# aa8028.net
KiCad netlist of a schematic drawn in Altium Designer
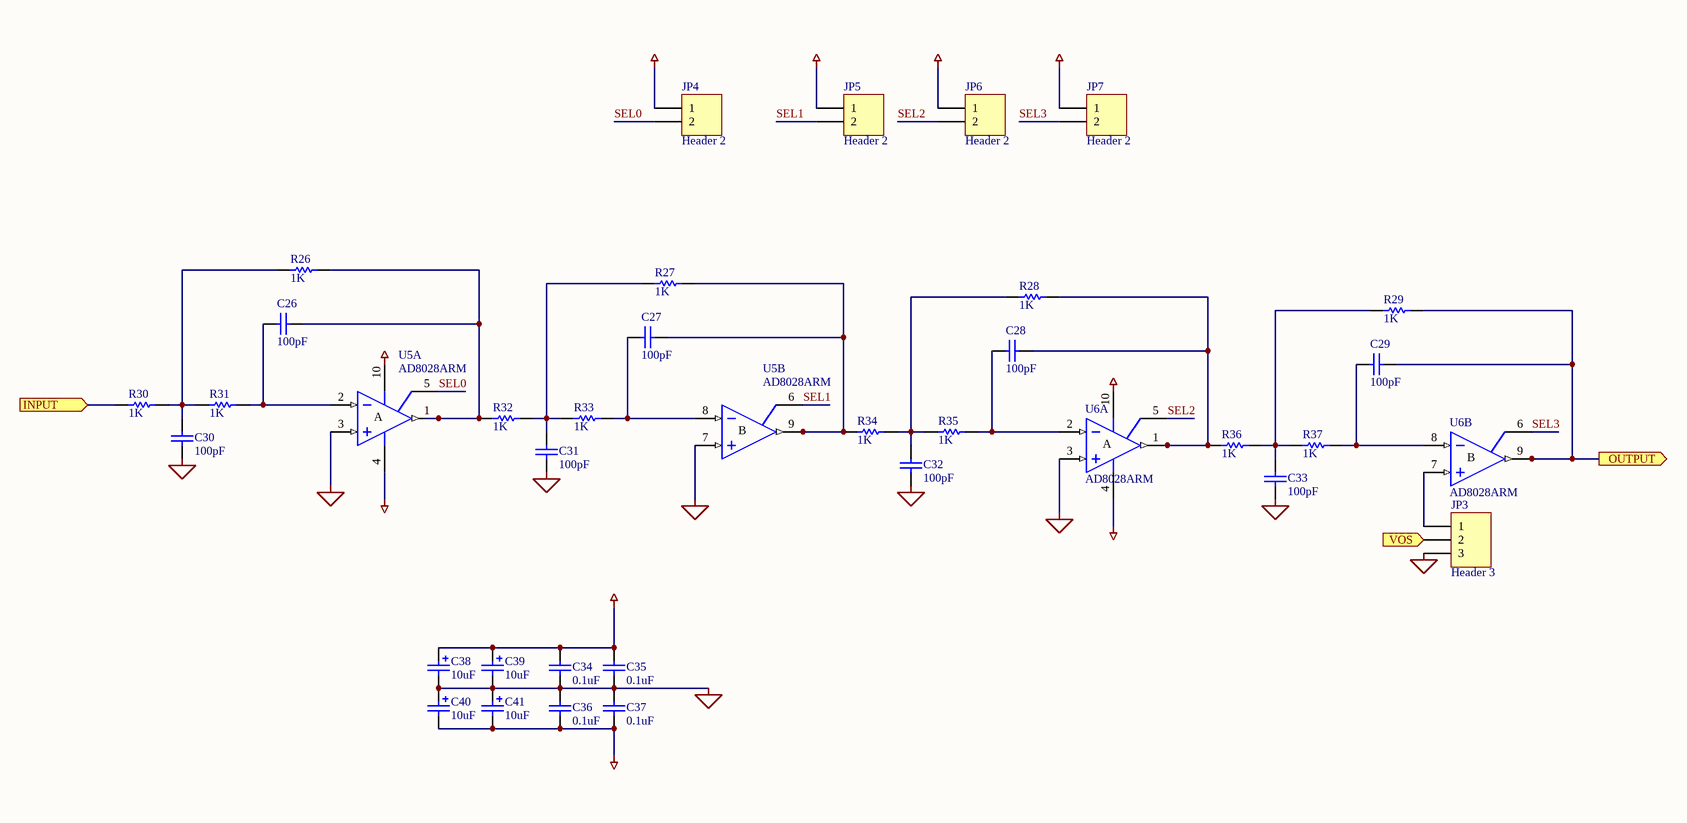
[diagram p0: aa8028.SCHDOC]

(export (version "E")
  (design (tool "Eeschema 10.0.6"))
  (components
    (comp (ref "C26")
      (value "Cap")
      (footprint "CC3216-1206")
      (description "Capacitor")
      (fields
        (field (name "MANUFACTURER") "Generic Components")
        (field (name "ALTIUM_VALUE") "100pF")
        (field (name "PUBLISHER") "Altium Limited")
      )
      (libsource (lib "Miscellaneous Devices") (part "Cap"))
    )
    (comp (ref "C27")
      (value "Cap")
      (footprint "CC3216-1206")
      (description "Capacitor")
      (fields
        (field (name "MANUFACTURER") "Generic Components")
        (field (name "ALTIUM_VALUE") "100pF")
        (field (name "PUBLISHER") "Altium Limited")
      )
      (libsource (lib "Miscellaneous Devices") (part "Cap"))
    )
    (comp (ref "C28")
      (value "Cap")
      (footprint "CC3216-1206")
      (description "Capacitor")
      (fields
        (field (name "MANUFACTURER") "Generic Components")
        (field (name "ALTIUM_VALUE") "100pF")
        (field (name "PUBLISHER") "Altium Limited")
      )
      (libsource (lib "Miscellaneous Devices") (part "Cap"))
    )
    (comp (ref "C29")
      (value "Cap")
      (footprint "CC3216-1206")
      (description "Capacitor")
      (fields
        (field (name "MANUFACTURER") "Generic Components")
        (field (name "ALTIUM_VALUE") "100pF")
        (field (name "PUBLISHER") "Altium Limited")
      )
      (libsource (lib "Miscellaneous Devices") (part "Cap"))
    )
    (comp (ref "C30")
      (value "Cap")
      (footprint "CC3216-1206")
      (description "Capacitor")
      (fields
        (field (name "MANUFACTURER") "Generic Components")
        (field (name "ALTIUM_VALUE") "100pF")
        (field (name "PUBLISHER") "Altium Limited")
      )
      (libsource (lib "Miscellaneous Devices") (part "Cap"))
    )
    (comp (ref "C31")
      (value "Cap")
      (footprint "CC3216-1206")
      (description "Capacitor")
      (fields
        (field (name "MANUFACTURER") "Generic Components")
        (field (name "ALTIUM_VALUE") "100pF")
        (field (name "PUBLISHER") "Altium Limited")
      )
      (libsource (lib "Miscellaneous Devices") (part "Cap"))
    )
    (comp (ref "C32")
      (value "Cap")
      (footprint "CC3216-1206")
      (description "Capacitor")
      (fields
        (field (name "MANUFACTURER") "Generic Components")
        (field (name "ALTIUM_VALUE") "100pF")
        (field (name "PUBLISHER") "Altium Limited")
      )
      (libsource (lib "Miscellaneous Devices") (part "Cap"))
    )
    (comp (ref "C33")
      (value "Cap")
      (footprint "CC3216-1206")
      (description "Capacitor")
      (fields
        (field (name "MANUFACTURER") "Generic Components")
        (field (name "ALTIUM_VALUE") "100pF")
        (field (name "PUBLISHER") "Altium Limited")
      )
      (libsource (lib "Miscellaneous Devices") (part "Cap"))
    )
    (comp (ref "C34")
      (value "Cap")
      (footprint "CC1608-0603")
      (description "Capacitor")
      (fields
        (field (name "MANUFACTURER") "Generic Components")
        (field (name "ALTIUM_VALUE") "0.1uF")
        (field (name "PUBLISHER") "Altium Limited")
      )
      (libsource (lib "Miscellaneous Devices") (part "Cap"))
    )
    (comp (ref "C35")
      (value "Cap")
      (footprint "CC1608-0603")
      (description "Capacitor")
      (fields
        (field (name "MANUFACTURER") "Generic Components")
        (field (name "ALTIUM_VALUE") "0.1uF")
        (field (name "PUBLISHER") "Altium Limited")
      )
      (libsource (lib "Miscellaneous Devices") (part "Cap"))
    )
    (comp (ref "C36")
      (value "Cap")
      (footprint "CC1608-0603")
      (description "Capacitor")
      (fields
        (field (name "MANUFACTURER") "Generic Components")
        (field (name "ALTIUM_VALUE") "0.1uF")
        (field (name "PUBLISHER") "Altium Limited")
      )
      (libsource (lib "Miscellaneous Devices") (part "Cap"))
    )
    (comp (ref "C37")
      (value "Cap")
      (footprint "CC1608-0603")
      (description "Capacitor")
      (fields
        (field (name "MANUFACTURER") "Generic Components")
        (field (name "ALTIUM_VALUE") "0.1uF")
        (field (name "PUBLISHER") "Altium Limited")
      )
      (libsource (lib "Miscellaneous Devices") (part "Cap"))
    )
    (comp (ref "C38")
      (value "Cap Pol1")
      (footprint "TC7360-2924")
      (description "Polarized Capacitor (Radial)")
      (fields
        (field (name "MANUFACTURER") "Generic Components")
        (field (name "ALTIUM_VALUE") "10uF")
        (field (name "PUBLISHER") "Altium Limited")
      )
      (libsource (lib "Miscellaneous Devices") (part "Cap Pol1"))
    )
    (comp (ref "C39")
      (value "Cap Pol1")
      (footprint "TC7360-2924")
      (description "Polarized Capacitor (Radial)")
      (fields
        (field (name "MANUFACTURER") "Generic Components")
        (field (name "ALTIUM_VALUE") "10uF")
        (field (name "PUBLISHER") "Altium Limited")
      )
      (libsource (lib "Miscellaneous Devices") (part "Cap Pol1"))
    )
    (comp (ref "C40")
      (value "Cap Pol1")
      (footprint "TC7360-2924")
      (description "Polarized Capacitor (Radial)")
      (fields
        (field (name "MANUFACTURER") "Generic Components")
        (field (name "ALTIUM_VALUE") "10uF")
        (field (name "PUBLISHER") "Altium Limited")
      )
      (libsource (lib "Miscellaneous Devices") (part "Cap Pol1"))
    )
    (comp (ref "C41")
      (value "Cap Pol1")
      (footprint "TC7360-2924")
      (description "Polarized Capacitor (Radial)")
      (fields
        (field (name "MANUFACTURER") "Generic Components")
        (field (name "ALTIUM_VALUE") "10uF")
        (field (name "PUBLISHER") "Altium Limited")
      )
      (libsource (lib "Miscellaneous Devices") (part "Cap Pol1"))
    )
    (comp (ref "JP3")
      (value "Header 3")
      (footprint "HDR1X3")
      (description "Header, 3-Pin")
      (fields (field (name "MANUFACTURER") "Generic Components") (field (name "PUBLISHER") "Altium Limited"))
      (libsource (lib "Miscellaneous Connectors") (part "Header 3"))
    )
    (comp (ref "JP4")
      (value "Header 2")
      (footprint "HDR1X2")
      (description "Header, 2-Pin")
      (fields (field (name "MANUFACTURER") "Generic Components") (field (name "PUBLISHER") "Altium Limited"))
      (libsource (lib "Miscellaneous Connectors") (part "Header 2"))
    )
    (comp (ref "JP5")
      (value "Header 2")
      (footprint "HDR1X2")
      (description "Header, 2-Pin")
      (fields (field (name "MANUFACTURER") "Generic Components") (field (name "PUBLISHER") "Altium Limited"))
      (libsource (lib "Miscellaneous Connectors") (part "Header 2"))
    )
    (comp (ref "JP6")
      (value "Header 2")
      (footprint "HDR1X2")
      (description "Header, 2-Pin")
      (fields (field (name "MANUFACTURER") "Generic Components") (field (name "PUBLISHER") "Altium Limited"))
      (libsource (lib "Miscellaneous Connectors") (part "Header 2"))
    )
    (comp (ref "JP7")
      (value "Header 2")
      (footprint "HDR1X2")
      (description "Header, 2-Pin")
      (fields (field (name "MANUFACTURER") "Generic Components") (field (name "PUBLISHER") "Altium Limited"))
      (libsource (lib "Miscellaneous Connectors") (part "Header 2"))
    )
    (comp (ref "R26")
      (value "Res1")
      (footprint "CC2012-0805")
      (description "Resistor")
      (fields
        (field (name "MANUFACTURER") "Generic Components")
        (field (name "ALTIUM_VALUE") "1K")
        (field (name "PUBLISHER") "Altium Limited")
      )
      (libsource (lib "Miscellaneous Devices") (part "Res1"))
    )
    (comp (ref "R27")
      (value "Res1")
      (footprint "CC2012-0805")
      (description "Resistor")
      (fields
        (field (name "MANUFACTURER") "Generic Components")
        (field (name "ALTIUM_VALUE") "1K")
        (field (name "PUBLISHER") "Altium Limited")
      )
      (libsource (lib "Miscellaneous Devices") (part "Res1"))
    )
    (comp (ref "R28")
      (value "Res1")
      (footprint "CC2012-0805")
      (description "Resistor")
      (fields
        (field (name "MANUFACTURER") "Generic Components")
        (field (name "ALTIUM_VALUE") "1K")
        (field (name "PUBLISHER") "Altium Limited")
      )
      (libsource (lib "Miscellaneous Devices") (part "Res1"))
    )
    (comp (ref "R29")
      (value "Res1")
      (footprint "CC2012-0805")
      (description "Resistor")
      (fields
        (field (name "MANUFACTURER") "Generic Components")
        (field (name "ALTIUM_VALUE") "1K")
        (field (name "PUBLISHER") "Altium Limited")
      )
      (libsource (lib "Miscellaneous Devices") (part "Res1"))
    )
    (comp (ref "R30")
      (value "Res1")
      (footprint "CC2012-0805")
      (description "Resistor")
      (fields
        (field (name "MANUFACTURER") "Generic Components")
        (field (name "ALTIUM_VALUE") "1K")
        (field (name "PUBLISHER") "Altium Limited")
      )
      (libsource (lib "Miscellaneous Devices") (part "Res1"))
    )
    (comp (ref "R31")
      (value "Res1")
      (footprint "CC2012-0805")
      (description "Resistor")
      (fields
        (field (name "MANUFACTURER") "Generic Components")
        (field (name "ALTIUM_VALUE") "1K")
        (field (name "PUBLISHER") "Altium Limited")
      )
      (libsource (lib "Miscellaneous Devices") (part "Res1"))
    )
    (comp (ref "R32")
      (value "Res1")
      (footprint "CC2012-0805")
      (description "Resistor")
      (fields
        (field (name "MANUFACTURER") "Generic Components")
        (field (name "ALTIUM_VALUE") "1K")
        (field (name "PUBLISHER") "Altium Limited")
      )
      (libsource (lib "Miscellaneous Devices") (part "Res1"))
    )
    (comp (ref "R33")
      (value "Res1")
      (footprint "CC2012-0805")
      (description "Resistor")
      (fields
        (field (name "MANUFACTURER") "Generic Components")
        (field (name "ALTIUM_VALUE") "1K")
        (field (name "PUBLISHER") "Altium Limited")
      )
      (libsource (lib "Miscellaneous Devices") (part "Res1"))
    )
    (comp (ref "R34")
      (value "Res1")
      (footprint "CC2012-0805")
      (description "Resistor")
      (fields
        (field (name "MANUFACTURER") "Generic Components")
        (field (name "ALTIUM_VALUE") "1K")
        (field (name "PUBLISHER") "Altium Limited")
      )
      (libsource (lib "Miscellaneous Devices") (part "Res1"))
    )
    (comp (ref "R35")
      (value "Res1")
      (footprint "CC2012-0805")
      (description "Resistor")
      (fields
        (field (name "MANUFACTURER") "Generic Components")
        (field (name "ALTIUM_VALUE") "1K")
        (field (name "PUBLISHER") "Altium Limited")
      )
      (libsource (lib "Miscellaneous Devices") (part "Res1"))
    )
    (comp (ref "R36")
      (value "Res1")
      (footprint "CC2012-0805")
      (description "Resistor")
      (fields
        (field (name "MANUFACTURER") "Generic Components")
        (field (name "ALTIUM_VALUE") "1K")
        (field (name "PUBLISHER") "Altium Limited")
      )
      (libsource (lib "Miscellaneous Devices") (part "Res1"))
    )
    (comp (ref "R37")
      (value "Res1")
      (footprint "CC2012-0805")
      (description "Resistor")
      (fields
        (field (name "MANUFACTURER") "Generic Components")
        (field (name "ALTIUM_VALUE") "1K")
        (field (name "PUBLISHER") "Altium Limited")
      )
      (libsource (lib "Miscellaneous Devices") (part "Res1"))
    )
    (comp (ref "U5")
      (value "AD8028ARM")
      (footprint "TSSO3x5-G10")
      (description "Analog Devices Low Distortion, High Speed RRIO OA")
      (libsource (lib "My devices") (part "AD8028ARM"))
    )
    (comp (ref "U6")
      (value "AD8028ARM")
      (footprint "TSSO3x5-G10")
      (description "Analog Devices Low Distortion, High Speed RRIO OA")
      (libsource (lib "My devices") (part "AD8028ARM"))
    )
  )
  (nets
    (net (code "1") (name "/INPUT") (class "Default")
      (node (ref "R30") (pin "1") (pinfunction "1_1") (pintype "passive"))
    )
    (net (code "2") (name "/OUTPUT") (class "Default")
      (node (ref "C29") (pin "1") (pinfunction "1_1") (pintype "passive"))
      (node (ref "R29") (pin "1") (pinfunction "1_1") (pintype "passive"))
      (node (ref "U6") (pin "9") (pinfunction "VOUTB_9") (pintype "output"))
    )
    (net (code "3") (name "/SEL0") (class "Default")
      (node (ref "JP4") (pin "2") (pinfunction "2_2") (pintype "passive"))
      (node (ref "U5") (pin "5") (pinfunction "SELA_5") (pintype "passive"))
    )
    (net (code "4") (name "/SEL1") (class "Default")
      (node (ref "JP5") (pin "2") (pinfunction "2_2") (pintype "passive"))
      (node (ref "U5") (pin "6") (pinfunction "SELB_6") (pintype "passive"))
    )
    (net (code "5") (name "/SEL2") (class "Default")
      (node (ref "JP6") (pin "2") (pinfunction "2_2") (pintype "passive"))
      (node (ref "U6") (pin "5") (pinfunction "SELA_5") (pintype "passive"))
    )
    (net (code "6") (name "/SEL3") (class "Default")
      (node (ref "JP7") (pin "2") (pinfunction "2_2") (pintype "passive"))
      (node (ref "U6") (pin "6") (pinfunction "SELB_6") (pintype "passive"))
    )
    (net (code "7") (name "/VOS") (class "Default")
      (node (ref "JP3") (pin "2") (pinfunction "2_2") (pintype "passive"))
    )
    (net (code "8") (name "AVDD") (class "Default")
      (node (ref "C34") (pin "2") (pinfunction "2_2") (pintype "passive"))
      (node (ref "C35") (pin "2") (pinfunction "2_2") (pintype "passive"))
      (node (ref "C38") (pin "1") (pinfunction "1_1") (pintype "passive"))
      (node (ref "C39") (pin "1") (pinfunction "1_1") (pintype "passive"))
      (node (ref "JP4") (pin "1") (pinfunction "1_1") (pintype "passive"))
      (node (ref "JP5") (pin "1") (pinfunction "1_1") (pintype "passive"))
      (node (ref "JP6") (pin "1") (pinfunction "1_1") (pintype "passive"))
      (node (ref "JP7") (pin "1") (pinfunction "1_1") (pintype "passive"))
      (node (ref "U5") (pin "10") (pinfunction "V+_10") (pintype "power_in"))
      (node (ref "U6") (pin "10") (pinfunction "V+_10") (pintype "power_in"))
    )
    (net (code "9") (name "AVSS") (class "Default")
      (node (ref "C36") (pin "1") (pinfunction "1_1") (pintype "passive"))
      (node (ref "C37") (pin "1") (pinfunction "1_1") (pintype "passive"))
      (node (ref "C40") (pin "2") (pinfunction "2_2") (pintype "passive"))
      (node (ref "C41") (pin "2") (pinfunction "2_2") (pintype "passive"))
      (node (ref "U5") (pin "4") (pinfunction "V-_4") (pintype "power_in"))
      (node (ref "U6") (pin "4") (pinfunction "V-_4") (pintype "power_in"))
    )
    (net (code "10") (name "GND") (class "Default")
      (node (ref "C30") (pin "1") (pinfunction "1_1") (pintype "passive"))
      (node (ref "C31") (pin "1") (pinfunction "1_1") (pintype "passive"))
      (node (ref "C32") (pin "1") (pinfunction "1_1") (pintype "passive"))
      (node (ref "C33") (pin "1") (pinfunction "1_1") (pintype "passive"))
      (node (ref "C34") (pin "1") (pinfunction "1_1") (pintype "passive"))
      (node (ref "C35") (pin "1") (pinfunction "1_1") (pintype "passive"))
      (node (ref "C36") (pin "2") (pinfunction "2_2") (pintype "passive"))
      (node (ref "C37") (pin "2") (pinfunction "2_2") (pintype "passive"))
      (node (ref "C38") (pin "2") (pinfunction "2_2") (pintype "passive"))
      (node (ref "C39") (pin "2") (pinfunction "2_2") (pintype "passive"))
      (node (ref "C40") (pin "1") (pinfunction "1_1") (pintype "passive"))
      (node (ref "C41") (pin "1") (pinfunction "1_1") (pintype "passive"))
      (node (ref "JP3") (pin "3") (pinfunction "3_3") (pintype "passive"))
      (node (ref "U5") (pin "3") (pinfunction "IN+A_3") (pintype "input"))
      (node (ref "U5") (pin "7") (pinfunction "IN+B_7") (pintype "input"))
      (node (ref "U6") (pin "3") (pinfunction "IN+A_3") (pintype "input"))
    )
    (net (code "11") (name "Net-(C30-Pad2)") (class "Default")
      (node (ref "C30") (pin "2") (pinfunction "2_2") (pintype "passive"))
      (node (ref "R26") (pin "2") (pinfunction "2_2") (pintype "passive"))
      (node (ref "R30") (pin "2") (pinfunction "2_2") (pintype "passive"))
      (node (ref "R31") (pin "1") (pinfunction "1_1") (pintype "passive"))
    )
    (net (code "12") (name "Net-(C31-Pad2)") (class "Default")
      (node (ref "C31") (pin "2") (pinfunction "2_2") (pintype "passive"))
      (node (ref "R27") (pin "2") (pinfunction "2_2") (pintype "passive"))
      (node (ref "R32") (pin "2") (pinfunction "2_2") (pintype "passive"))
      (node (ref "R33") (pin "1") (pinfunction "1_1") (pintype "passive"))
    )
    (net (code "13") (name "Net-(C32-Pad2)") (class "Default")
      (node (ref "C32") (pin "2") (pinfunction "2_2") (pintype "passive"))
      (node (ref "R28") (pin "2") (pinfunction "2_2") (pintype "passive"))
      (node (ref "R34") (pin "2") (pinfunction "2_2") (pintype "passive"))
      (node (ref "R35") (pin "1") (pinfunction "1_1") (pintype "passive"))
    )
    (net (code "14") (name "Net-(C33-Pad2)") (class "Default")
      (node (ref "C33") (pin "2") (pinfunction "2_2") (pintype "passive"))
      (node (ref "R29") (pin "2") (pinfunction "2_2") (pintype "passive"))
      (node (ref "R36") (pin "2") (pinfunction "2_2") (pintype "passive"))
      (node (ref "R37") (pin "1") (pinfunction "1_1") (pintype "passive"))
    )
    (net (code "15") (name "Net-(U5A-IN-A)") (class "Default")
      (node (ref "C26") (pin "2") (pinfunction "2_2") (pintype "passive"))
      (node (ref "R31") (pin "2") (pinfunction "2_2") (pintype "passive"))
      (node (ref "U5") (pin "2") (pinfunction "IN-A_2") (pintype "input"))
    )
    (net (code "16") (name "Net-(U5A-VOUTA)") (class "Default")
      (node (ref "C26") (pin "1") (pinfunction "1_1") (pintype "passive"))
      (node (ref "R26") (pin "1") (pinfunction "1_1") (pintype "passive"))
      (node (ref "R32") (pin "1") (pinfunction "1_1") (pintype "passive"))
      (node (ref "U5") (pin "1") (pinfunction "VOUTA_1") (pintype "output"))
    )
    (net (code "17") (name "Net-(U5B-IN-B)") (class "Default")
      (node (ref "C27") (pin "2") (pinfunction "2_2") (pintype "passive"))
      (node (ref "R33") (pin "2") (pinfunction "2_2") (pintype "passive"))
      (node (ref "U5") (pin "8") (pinfunction "IN-B_8") (pintype "input"))
    )
    (net (code "18") (name "Net-(U5B-VOUTB)") (class "Default")
      (node (ref "C27") (pin "1") (pinfunction "1_1") (pintype "passive"))
      (node (ref "R27") (pin "1") (pinfunction "1_1") (pintype "passive"))
      (node (ref "R34") (pin "1") (pinfunction "1_1") (pintype "passive"))
      (node (ref "U5") (pin "9") (pinfunction "VOUTB_9") (pintype "output"))
    )
    (net (code "19") (name "Net-(U6A-IN-A)") (class "Default")
      (node (ref "C28") (pin "2") (pinfunction "2_2") (pintype "passive"))
      (node (ref "R35") (pin "2") (pinfunction "2_2") (pintype "passive"))
      (node (ref "U6") (pin "2") (pinfunction "IN-A_2") (pintype "input"))
    )
    (net (code "20") (name "Net-(U6A-VOUTA)") (class "Default")
      (node (ref "C28") (pin "1") (pinfunction "1_1") (pintype "passive"))
      (node (ref "R28") (pin "1") (pinfunction "1_1") (pintype "passive"))
      (node (ref "R36") (pin "1") (pinfunction "1_1") (pintype "passive"))
      (node (ref "U6") (pin "1") (pinfunction "VOUTA_1") (pintype "output"))
    )
    (net (code "21") (name "Net-(U6B-IN+B)") (class "Default")
      (node (ref "JP3") (pin "1") (pinfunction "1_1") (pintype "passive"))
      (node (ref "U6") (pin "7") (pinfunction "IN+B_7") (pintype "input"))
    )
    (net (code "22") (name "Net-(U6B-IN-B)") (class "Default")
      (node (ref "C29") (pin "2") (pinfunction "2_2") (pintype "passive"))
      (node (ref "R37") (pin "2") (pinfunction "2_2") (pintype "passive"))
      (node (ref "U6") (pin "8") (pinfunction "IN-B_8") (pintype "input"))
    )
  )
)
